# proto.net
KiCad netlist of a schematic drawn in EAGLE
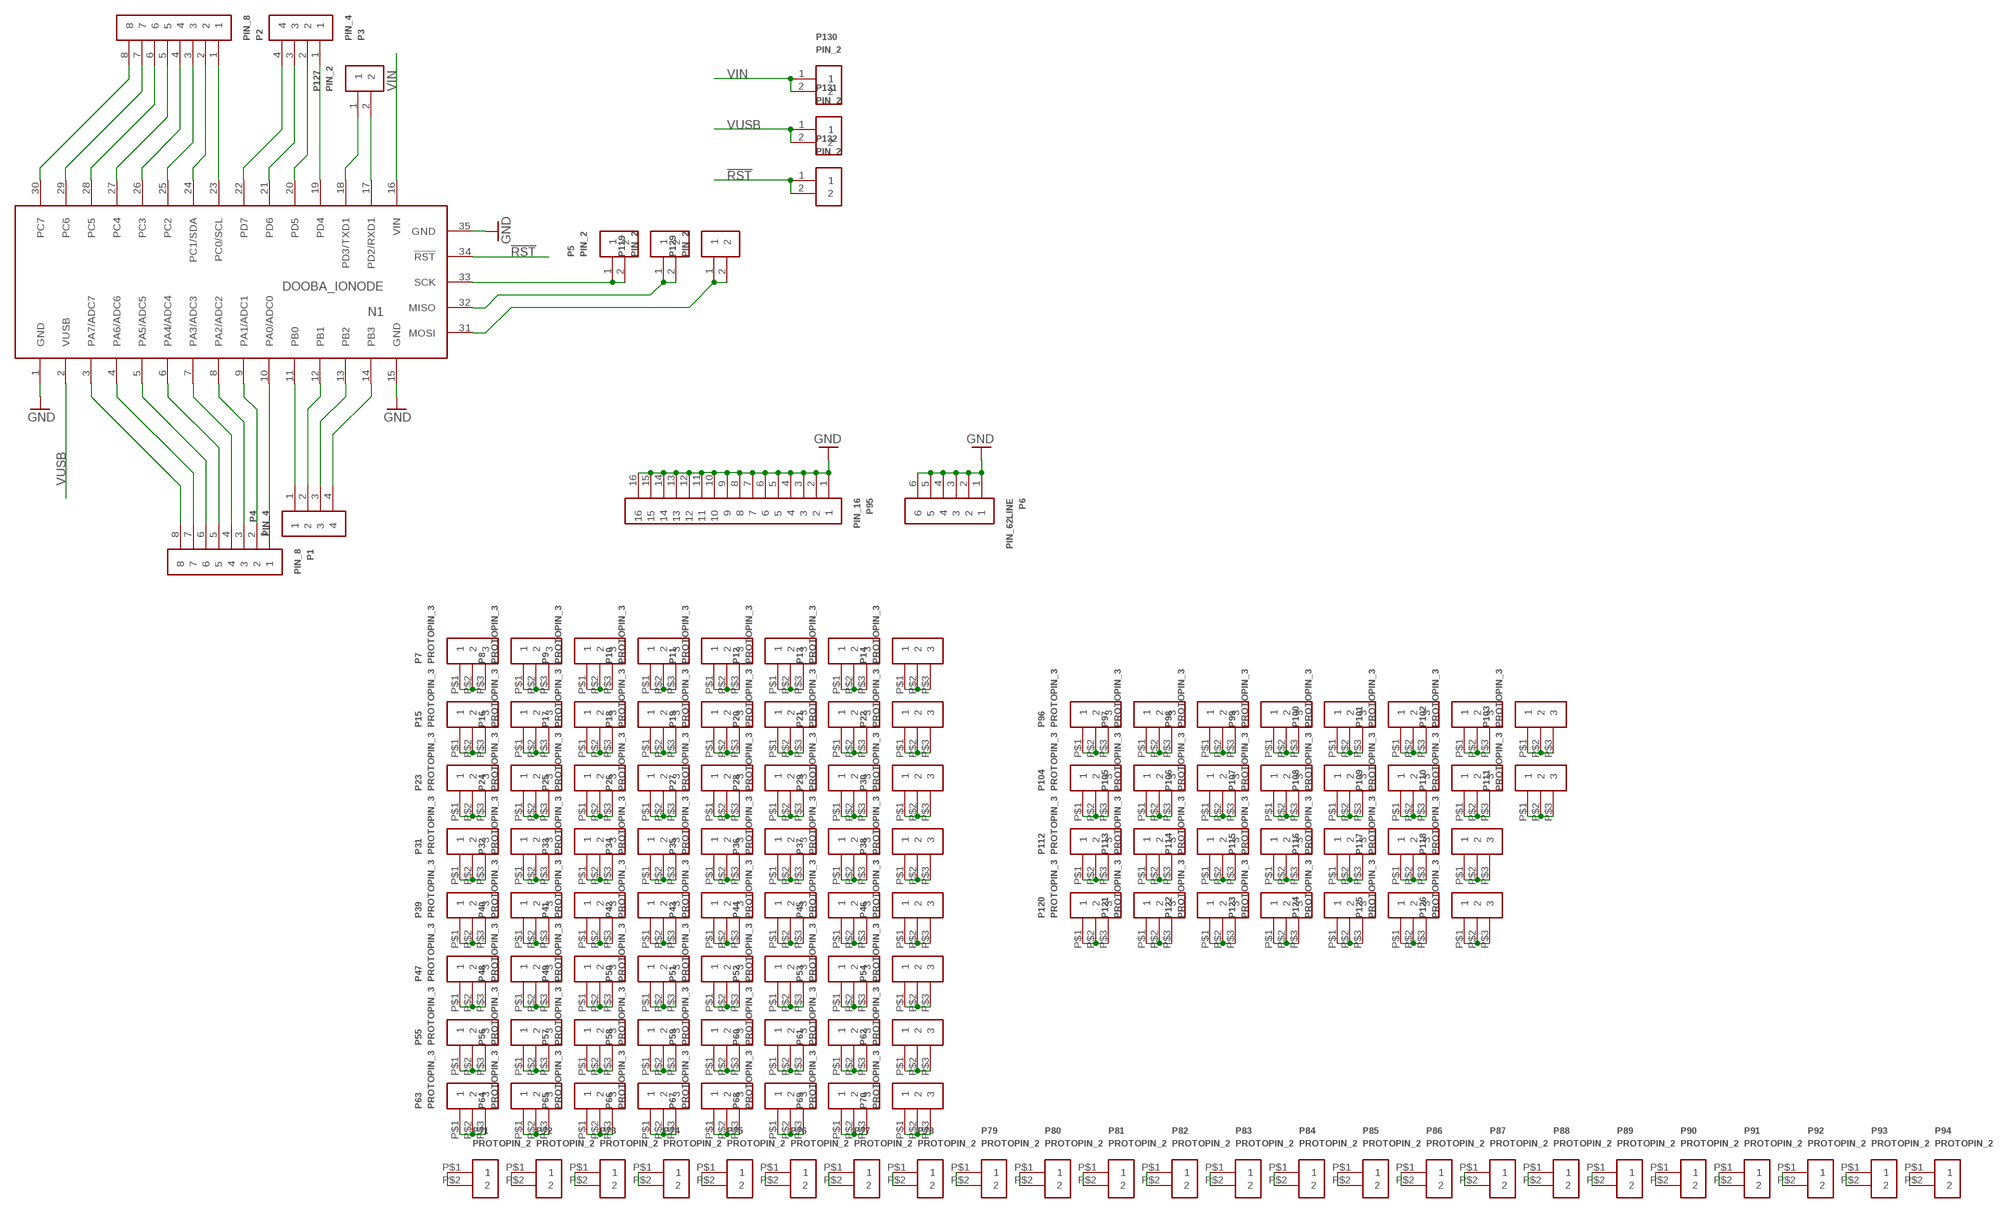
[diagram p0: schematic, sheet 1]

(export (version "E")
  (design (tool "Eeschema 10.0.6"))
  (components
    (comp (ref "N1")
      (value "DOOBA_IONODE")
      (footprint "eagle-import:DOOBA_IONODE")
      (libsource (lib "eagle-import") (part "DOOBA_IONODE"))
    )
    (comp (ref "P1")
      (value "PIN_8")
      (footprint "eagle-import:PIN_8")
      (libsource (lib "eagle-import") (part "PIN_8"))
    )
    (comp (ref "P2")
      (value "PIN_8")
      (footprint "eagle-import:PIN_8")
      (libsource (lib "eagle-import") (part "PIN_8"))
    )
    (comp (ref "P3")
      (value "PIN_4")
      (footprint "eagle-import:PIN_4")
      (libsource (lib "eagle-import") (part "PIN_4"))
    )
    (comp (ref "P4")
      (value "PIN_4")
      (footprint "eagle-import:PIN_4")
      (libsource (lib "eagle-import") (part "PIN_4"))
    )
    (comp (ref "P5")
      (value "PIN_2")
      (footprint "eagle-import:PIN_2")
      (libsource (lib "eagle-import") (part "PIN_2"))
    )
    (comp (ref "P6")
      (value "PIN_62LINE")
      (footprint "eagle-import:PIN_3X2")
      (libsource (lib "eagle-import") (part "PIN_62LINE"))
    )
    (comp (ref "P7")
      (value "PROTOPIN_3")
      (footprint "eagle-import:PROTOPIN_3")
      (libsource (lib "eagle-import") (part "PROTOPIN_3"))
    )
    (comp (ref "P8")
      (value "PROTOPIN_3")
      (footprint "eagle-import:PROTOPIN_3")
      (libsource (lib "eagle-import") (part "PROTOPIN_3"))
    )
    (comp (ref "P9")
      (value "PROTOPIN_3")
      (footprint "eagle-import:PROTOPIN_3")
      (libsource (lib "eagle-import") (part "PROTOPIN_3"))
    )
    (comp (ref "P10")
      (value "PROTOPIN_3")
      (footprint "eagle-import:PROTOPIN_3")
      (libsource (lib "eagle-import") (part "PROTOPIN_3"))
    )
    (comp (ref "P11")
      (value "PROTOPIN_3")
      (footprint "eagle-import:PROTOPIN_3")
      (libsource (lib "eagle-import") (part "PROTOPIN_3"))
    )
    (comp (ref "P12")
      (value "PROTOPIN_3")
      (footprint "eagle-import:PROTOPIN_3")
      (libsource (lib "eagle-import") (part "PROTOPIN_3"))
    )
    (comp (ref "P13")
      (value "PROTOPIN_3")
      (footprint "eagle-import:PROTOPIN_3")
      (libsource (lib "eagle-import") (part "PROTOPIN_3"))
    )
    (comp (ref "P14")
      (value "PROTOPIN_3")
      (footprint "eagle-import:PROTOPIN_3")
      (libsource (lib "eagle-import") (part "PROTOPIN_3"))
    )
    (comp (ref "P15")
      (value "PROTOPIN_3")
      (footprint "eagle-import:PROTOPIN_3")
      (libsource (lib "eagle-import") (part "PROTOPIN_3"))
    )
    (comp (ref "P16")
      (value "PROTOPIN_3")
      (footprint "eagle-import:PROTOPIN_3")
      (libsource (lib "eagle-import") (part "PROTOPIN_3"))
    )
    (comp (ref "P17")
      (value "PROTOPIN_3")
      (footprint "eagle-import:PROTOPIN_3")
      (libsource (lib "eagle-import") (part "PROTOPIN_3"))
    )
    (comp (ref "P18")
      (value "PROTOPIN_3")
      (footprint "eagle-import:PROTOPIN_3")
      (libsource (lib "eagle-import") (part "PROTOPIN_3"))
    )
    (comp (ref "P19")
      (value "PROTOPIN_3")
      (footprint "eagle-import:PROTOPIN_3")
      (libsource (lib "eagle-import") (part "PROTOPIN_3"))
    )
    (comp (ref "P20")
      (value "PROTOPIN_3")
      (footprint "eagle-import:PROTOPIN_3")
      (libsource (lib "eagle-import") (part "PROTOPIN_3"))
    )
    (comp (ref "P21")
      (value "PROTOPIN_3")
      (footprint "eagle-import:PROTOPIN_3")
      (libsource (lib "eagle-import") (part "PROTOPIN_3"))
    )
    (comp (ref "P22")
      (value "PROTOPIN_3")
      (footprint "eagle-import:PROTOPIN_3")
      (libsource (lib "eagle-import") (part "PROTOPIN_3"))
    )
    (comp (ref "P23")
      (value "PROTOPIN_3")
      (footprint "eagle-import:PROTOPIN_3")
      (libsource (lib "eagle-import") (part "PROTOPIN_3"))
    )
    (comp (ref "P24")
      (value "PROTOPIN_3")
      (footprint "eagle-import:PROTOPIN_3")
      (libsource (lib "eagle-import") (part "PROTOPIN_3"))
    )
    (comp (ref "P25")
      (value "PROTOPIN_3")
      (footprint "eagle-import:PROTOPIN_3")
      (libsource (lib "eagle-import") (part "PROTOPIN_3"))
    )
    (comp (ref "P26")
      (value "PROTOPIN_3")
      (footprint "eagle-import:PROTOPIN_3")
      (libsource (lib "eagle-import") (part "PROTOPIN_3"))
    )
    (comp (ref "P27")
      (value "PROTOPIN_3")
      (footprint "eagle-import:PROTOPIN_3")
      (libsource (lib "eagle-import") (part "PROTOPIN_3"))
    )
    (comp (ref "P28")
      (value "PROTOPIN_3")
      (footprint "eagle-import:PROTOPIN_3")
      (libsource (lib "eagle-import") (part "PROTOPIN_3"))
    )
    (comp (ref "P29")
      (value "PROTOPIN_3")
      (footprint "eagle-import:PROTOPIN_3")
      (libsource (lib "eagle-import") (part "PROTOPIN_3"))
    )
    (comp (ref "P30")
      (value "PROTOPIN_3")
      (footprint "eagle-import:PROTOPIN_3")
      (libsource (lib "eagle-import") (part "PROTOPIN_3"))
    )
    (comp (ref "P31")
      (value "PROTOPIN_3")
      (footprint "eagle-import:PROTOPIN_3")
      (libsource (lib "eagle-import") (part "PROTOPIN_3"))
    )
    (comp (ref "P32")
      (value "PROTOPIN_3")
      (footprint "eagle-import:PROTOPIN_3")
      (libsource (lib "eagle-import") (part "PROTOPIN_3"))
    )
    (comp (ref "P33")
      (value "PROTOPIN_3")
      (footprint "eagle-import:PROTOPIN_3")
      (libsource (lib "eagle-import") (part "PROTOPIN_3"))
    )
    (comp (ref "P34")
      (value "PROTOPIN_3")
      (footprint "eagle-import:PROTOPIN_3")
      (libsource (lib "eagle-import") (part "PROTOPIN_3"))
    )
    (comp (ref "P35")
      (value "PROTOPIN_3")
      (footprint "eagle-import:PROTOPIN_3")
      (libsource (lib "eagle-import") (part "PROTOPIN_3"))
    )
    (comp (ref "P36")
      (value "PROTOPIN_3")
      (footprint "eagle-import:PROTOPIN_3")
      (libsource (lib "eagle-import") (part "PROTOPIN_3"))
    )
    (comp (ref "P37")
      (value "PROTOPIN_3")
      (footprint "eagle-import:PROTOPIN_3")
      (libsource (lib "eagle-import") (part "PROTOPIN_3"))
    )
    (comp (ref "P38")
      (value "PROTOPIN_3")
      (footprint "eagle-import:PROTOPIN_3")
      (libsource (lib "eagle-import") (part "PROTOPIN_3"))
    )
    (comp (ref "P39")
      (value "PROTOPIN_3")
      (footprint "eagle-import:PROTOPIN_3")
      (libsource (lib "eagle-import") (part "PROTOPIN_3"))
    )
    (comp (ref "P40")
      (value "PROTOPIN_3")
      (footprint "eagle-import:PROTOPIN_3")
      (libsource (lib "eagle-import") (part "PROTOPIN_3"))
    )
    (comp (ref "P41")
      (value "PROTOPIN_3")
      (footprint "eagle-import:PROTOPIN_3")
      (libsource (lib "eagle-import") (part "PROTOPIN_3"))
    )
    (comp (ref "P42")
      (value "PROTOPIN_3")
      (footprint "eagle-import:PROTOPIN_3")
      (libsource (lib "eagle-import") (part "PROTOPIN_3"))
    )
    (comp (ref "P43")
      (value "PROTOPIN_3")
      (footprint "eagle-import:PROTOPIN_3")
      (libsource (lib "eagle-import") (part "PROTOPIN_3"))
    )
    (comp (ref "P44")
      (value "PROTOPIN_3")
      (footprint "eagle-import:PROTOPIN_3")
      (libsource (lib "eagle-import") (part "PROTOPIN_3"))
    )
    (comp (ref "P45")
      (value "PROTOPIN_3")
      (footprint "eagle-import:PROTOPIN_3")
      (libsource (lib "eagle-import") (part "PROTOPIN_3"))
    )
    (comp (ref "P46")
      (value "PROTOPIN_3")
      (footprint "eagle-import:PROTOPIN_3")
      (libsource (lib "eagle-import") (part "PROTOPIN_3"))
    )
    (comp (ref "P47")
      (value "PROTOPIN_3")
      (footprint "eagle-import:PROTOPIN_3")
      (libsource (lib "eagle-import") (part "PROTOPIN_3"))
    )
    (comp (ref "P48")
      (value "PROTOPIN_3")
      (footprint "eagle-import:PROTOPIN_3")
      (libsource (lib "eagle-import") (part "PROTOPIN_3"))
    )
    (comp (ref "P49")
      (value "PROTOPIN_3")
      (footprint "eagle-import:PROTOPIN_3")
      (libsource (lib "eagle-import") (part "PROTOPIN_3"))
    )
    (comp (ref "P50")
      (value "PROTOPIN_3")
      (footprint "eagle-import:PROTOPIN_3")
      (libsource (lib "eagle-import") (part "PROTOPIN_3"))
    )
    (comp (ref "P51")
      (value "PROTOPIN_3")
      (footprint "eagle-import:PROTOPIN_3")
      (libsource (lib "eagle-import") (part "PROTOPIN_3"))
    )
    (comp (ref "P52")
      (value "PROTOPIN_3")
      (footprint "eagle-import:PROTOPIN_3")
      (libsource (lib "eagle-import") (part "PROTOPIN_3"))
    )
    (comp (ref "P53")
      (value "PROTOPIN_3")
      (footprint "eagle-import:PROTOPIN_3")
      (libsource (lib "eagle-import") (part "PROTOPIN_3"))
    )
    (comp (ref "P54")
      (value "PROTOPIN_3")
      (footprint "eagle-import:PROTOPIN_3")
      (libsource (lib "eagle-import") (part "PROTOPIN_3"))
    )
    (comp (ref "P55")
      (value "PROTOPIN_3")
      (footprint "eagle-import:PROTOPIN_3")
      (libsource (lib "eagle-import") (part "PROTOPIN_3"))
    )
    (comp (ref "P56")
      (value "PROTOPIN_3")
      (footprint "eagle-import:PROTOPIN_3")
      (libsource (lib "eagle-import") (part "PROTOPIN_3"))
    )
    (comp (ref "P57")
      (value "PROTOPIN_3")
      (footprint "eagle-import:PROTOPIN_3")
      (libsource (lib "eagle-import") (part "PROTOPIN_3"))
    )
    (comp (ref "P58")
      (value "PROTOPIN_3")
      (footprint "eagle-import:PROTOPIN_3")
      (libsource (lib "eagle-import") (part "PROTOPIN_3"))
    )
    (comp (ref "P59")
      (value "PROTOPIN_3")
      (footprint "eagle-import:PROTOPIN_3")
      (libsource (lib "eagle-import") (part "PROTOPIN_3"))
    )
    (comp (ref "P60")
      (value "PROTOPIN_3")
      (footprint "eagle-import:PROTOPIN_3")
      (libsource (lib "eagle-import") (part "PROTOPIN_3"))
    )
    (comp (ref "P61")
      (value "PROTOPIN_3")
      (footprint "eagle-import:PROTOPIN_3")
      (libsource (lib "eagle-import") (part "PROTOPIN_3"))
    )
    (comp (ref "P62")
      (value "PROTOPIN_3")
      (footprint "eagle-import:PROTOPIN_3")
      (libsource (lib "eagle-import") (part "PROTOPIN_3"))
    )
    (comp (ref "P63")
      (value "PROTOPIN_3")
      (footprint "eagle-import:PROTOPIN_3")
      (libsource (lib "eagle-import") (part "PROTOPIN_3"))
    )
    (comp (ref "P64")
      (value "PROTOPIN_3")
      (footprint "eagle-import:PROTOPIN_3")
      (libsource (lib "eagle-import") (part "PROTOPIN_3"))
    )
    (comp (ref "P65")
      (value "PROTOPIN_3")
      (footprint "eagle-import:PROTOPIN_3")
      (libsource (lib "eagle-import") (part "PROTOPIN_3"))
    )
    (comp (ref "P66")
      (value "PROTOPIN_3")
      (footprint "eagle-import:PROTOPIN_3")
      (libsource (lib "eagle-import") (part "PROTOPIN_3"))
    )
    (comp (ref "P67")
      (value "PROTOPIN_3")
      (footprint "eagle-import:PROTOPIN_3")
      (libsource (lib "eagle-import") (part "PROTOPIN_3"))
    )
    (comp (ref "P68")
      (value "PROTOPIN_3")
      (footprint "eagle-import:PROTOPIN_3")
      (libsource (lib "eagle-import") (part "PROTOPIN_3"))
    )
    (comp (ref "P69")
      (value "PROTOPIN_3")
      (footprint "eagle-import:PROTOPIN_3")
      (libsource (lib "eagle-import") (part "PROTOPIN_3"))
    )
    (comp (ref "P70")
      (value "PROTOPIN_3")
      (footprint "eagle-import:PROTOPIN_3")
      (libsource (lib "eagle-import") (part "PROTOPIN_3"))
    )
    (comp (ref "P71")
      (value "PROTOPIN_2")
      (footprint "eagle-import:PROTOPIN_2")
      (libsource (lib "eagle-import") (part "PROTOPIN_2"))
    )
    (comp (ref "P72")
      (value "PROTOPIN_2")
      (footprint "eagle-import:PROTOPIN_2")
      (libsource (lib "eagle-import") (part "PROTOPIN_2"))
    )
    (comp (ref "P73")
      (value "PROTOPIN_2")
      (footprint "eagle-import:PROTOPIN_2")
      (libsource (lib "eagle-import") (part "PROTOPIN_2"))
    )
    (comp (ref "P74")
      (value "PROTOPIN_2")
      (footprint "eagle-import:PROTOPIN_2")
      (libsource (lib "eagle-import") (part "PROTOPIN_2"))
    )
    (comp (ref "P75")
      (value "PROTOPIN_2")
      (footprint "eagle-import:PROTOPIN_2")
      (libsource (lib "eagle-import") (part "PROTOPIN_2"))
    )
    (comp (ref "P76")
      (value "PROTOPIN_2")
      (footprint "eagle-import:PROTOPIN_2")
      (libsource (lib "eagle-import") (part "PROTOPIN_2"))
    )
    (comp (ref "P77")
      (value "PROTOPIN_2")
      (footprint "eagle-import:PROTOPIN_2")
      (libsource (lib "eagle-import") (part "PROTOPIN_2"))
    )
    (comp (ref "P78")
      (value "PROTOPIN_2")
      (footprint "eagle-import:PROTOPIN_2")
      (libsource (lib "eagle-import") (part "PROTOPIN_2"))
    )
    (comp (ref "P79")
      (value "PROTOPIN_2")
      (footprint "eagle-import:PROTOPIN_2")
      (libsource (lib "eagle-import") (part "PROTOPIN_2"))
    )
    (comp (ref "P80")
      (value "PROTOPIN_2")
      (footprint "eagle-import:PROTOPIN_2")
      (libsource (lib "eagle-import") (part "PROTOPIN_2"))
    )
    (comp (ref "P81")
      (value "PROTOPIN_2")
      (footprint "eagle-import:PROTOPIN_2")
      (libsource (lib "eagle-import") (part "PROTOPIN_2"))
    )
    (comp (ref "P82")
      (value "PROTOPIN_2")
      (footprint "eagle-import:PROTOPIN_2")
      (libsource (lib "eagle-import") (part "PROTOPIN_2"))
    )
    (comp (ref "P83")
      (value "PROTOPIN_2")
      (footprint "eagle-import:PROTOPIN_2")
      (libsource (lib "eagle-import") (part "PROTOPIN_2"))
    )
    (comp (ref "P84")
      (value "PROTOPIN_2")
      (footprint "eagle-import:PROTOPIN_2")
      (libsource (lib "eagle-import") (part "PROTOPIN_2"))
    )
    (comp (ref "P85")
      (value "PROTOPIN_2")
      (footprint "eagle-import:PROTOPIN_2")
      (libsource (lib "eagle-import") (part "PROTOPIN_2"))
    )
    (comp (ref "P86")
      (value "PROTOPIN_2")
      (footprint "eagle-import:PROTOPIN_2")
      (libsource (lib "eagle-import") (part "PROTOPIN_2"))
    )
    (comp (ref "P87")
      (value "PROTOPIN_2")
      (footprint "eagle-import:PROTOPIN_2")
      (libsource (lib "eagle-import") (part "PROTOPIN_2"))
    )
    (comp (ref "P88")
      (value "PROTOPIN_2")
      (footprint "eagle-import:PROTOPIN_2")
      (libsource (lib "eagle-import") (part "PROTOPIN_2"))
    )
    (comp (ref "P89")
      (value "PROTOPIN_2")
      (footprint "eagle-import:PROTOPIN_2")
      (libsource (lib "eagle-import") (part "PROTOPIN_2"))
    )
    (comp (ref "P90")
      (value "PROTOPIN_2")
      (footprint "eagle-import:PROTOPIN_2")
      (libsource (lib "eagle-import") (part "PROTOPIN_2"))
    )
    (comp (ref "P91")
      (value "PROTOPIN_2")
      (footprint "eagle-import:PROTOPIN_2")
      (libsource (lib "eagle-import") (part "PROTOPIN_2"))
    )
    (comp (ref "P92")
      (value "PROTOPIN_2")
      (footprint "eagle-import:PROTOPIN_2")
      (libsource (lib "eagle-import") (part "PROTOPIN_2"))
    )
    (comp (ref "P93")
      (value "PROTOPIN_2")
      (footprint "eagle-import:PROTOPIN_2")
      (libsource (lib "eagle-import") (part "PROTOPIN_2"))
    )
    (comp (ref "P94")
      (value "PROTOPIN_2")
      (footprint "eagle-import:PROTOPIN_2")
      (libsource (lib "eagle-import") (part "PROTOPIN_2"))
    )
    (comp (ref "P95")
      (value "PIN_16")
      (footprint "eagle-import:PIN_16")
      (libsource (lib "eagle-import") (part "PIN_16"))
    )
    (comp (ref "P96")
      (value "PROTOPIN_3")
      (footprint "eagle-import:PROTOPIN_3")
      (libsource (lib "eagle-import") (part "PROTOPIN_3"))
    )
    (comp (ref "P97")
      (value "PROTOPIN_3")
      (footprint "eagle-import:PROTOPIN_3")
      (libsource (lib "eagle-import") (part "PROTOPIN_3"))
    )
    (comp (ref "P98")
      (value "PROTOPIN_3")
      (footprint "eagle-import:PROTOPIN_3")
      (libsource (lib "eagle-import") (part "PROTOPIN_3"))
    )
    (comp (ref "P99")
      (value "PROTOPIN_3")
      (footprint "eagle-import:PROTOPIN_3")
      (libsource (lib "eagle-import") (part "PROTOPIN_3"))
    )
    (comp (ref "P100")
      (value "PROTOPIN_3")
      (footprint "eagle-import:PROTOPIN_3")
      (libsource (lib "eagle-import") (part "PROTOPIN_3"))
    )
    (comp (ref "P101")
      (value "PROTOPIN_3")
      (footprint "eagle-import:PROTOPIN_3")
      (libsource (lib "eagle-import") (part "PROTOPIN_3"))
    )
    (comp (ref "P102")
      (value "PROTOPIN_3")
      (footprint "eagle-import:PROTOPIN_3")
      (libsource (lib "eagle-import") (part "PROTOPIN_3"))
    )
    (comp (ref "P103")
      (value "PROTOPIN_3")
      (footprint "eagle-import:PROTOPIN_3")
      (libsource (lib "eagle-import") (part "PROTOPIN_3"))
    )
    (comp (ref "P104")
      (value "PROTOPIN_3")
      (footprint "eagle-import:PROTOPIN_3")
      (libsource (lib "eagle-import") (part "PROTOPIN_3"))
    )
    (comp (ref "P105")
      (value "PROTOPIN_3")
      (footprint "eagle-import:PROTOPIN_3")
      (libsource (lib "eagle-import") (part "PROTOPIN_3"))
    )
    (comp (ref "P106")
      (value "PROTOPIN_3")
      (footprint "eagle-import:PROTOPIN_3")
      (libsource (lib "eagle-import") (part "PROTOPIN_3"))
    )
    (comp (ref "P107")
      (value "PROTOPIN_3")
      (footprint "eagle-import:PROTOPIN_3")
      (libsource (lib "eagle-import") (part "PROTOPIN_3"))
    )
    (comp (ref "P108")
      (value "PROTOPIN_3")
      (footprint "eagle-import:PROTOPIN_3")
      (libsource (lib "eagle-import") (part "PROTOPIN_3"))
    )
    (comp (ref "P109")
      (value "PROTOPIN_3")
      (footprint "eagle-import:PROTOPIN_3")
      (libsource (lib "eagle-import") (part "PROTOPIN_3"))
    )
    (comp (ref "P110")
      (value "PROTOPIN_3")
      (footprint "eagle-import:PROTOPIN_3")
      (libsource (lib "eagle-import") (part "PROTOPIN_3"))
    )
    (comp (ref "P111")
      (value "PROTOPIN_3")
      (footprint "eagle-import:PROTOPIN_3")
      (libsource (lib "eagle-import") (part "PROTOPIN_3"))
    )
    (comp (ref "P112")
      (value "PROTOPIN_3")
      (footprint "eagle-import:PROTOPIN_3")
      (libsource (lib "eagle-import") (part "PROTOPIN_3"))
    )
    (comp (ref "P113")
      (value "PROTOPIN_3")
      (footprint "eagle-import:PROTOPIN_3")
      (libsource (lib "eagle-import") (part "PROTOPIN_3"))
    )
    (comp (ref "P114")
      (value "PROTOPIN_3")
      (footprint "eagle-import:PROTOPIN_3")
      (libsource (lib "eagle-import") (part "PROTOPIN_3"))
    )
    (comp (ref "P115")
      (value "PROTOPIN_3")
      (footprint "eagle-import:PROTOPIN_3")
      (libsource (lib "eagle-import") (part "PROTOPIN_3"))
    )
    (comp (ref "P116")
      (value "PROTOPIN_3")
      (footprint "eagle-import:PROTOPIN_3")
      (libsource (lib "eagle-import") (part "PROTOPIN_3"))
    )
    (comp (ref "P117")
      (value "PROTOPIN_3")
      (footprint "eagle-import:PROTOPIN_3")
      (libsource (lib "eagle-import") (part "PROTOPIN_3"))
    )
    (comp (ref "P118")
      (value "PROTOPIN_3")
      (footprint "eagle-import:PROTOPIN_3")
      (libsource (lib "eagle-import") (part "PROTOPIN_3"))
    )
    (comp (ref "P119")
      (value "PIN_2")
      (footprint "eagle-import:PIN_2")
      (libsource (lib "eagle-import") (part "PIN_2"))
    )
    (comp (ref "P120")
      (value "PROTOPIN_3")
      (footprint "eagle-import:PROTOPIN_3")
      (libsource (lib "eagle-import") (part "PROTOPIN_3"))
    )
    (comp (ref "P121")
      (value "PROTOPIN_3")
      (footprint "eagle-import:PROTOPIN_3")
      (libsource (lib "eagle-import") (part "PROTOPIN_3"))
    )
    (comp (ref "P122")
      (value "PROTOPIN_3")
      (footprint "eagle-import:PROTOPIN_3")
      (libsource (lib "eagle-import") (part "PROTOPIN_3"))
    )
    (comp (ref "P123")
      (value "PROTOPIN_3")
      (footprint "eagle-import:PROTOPIN_3")
      (libsource (lib "eagle-import") (part "PROTOPIN_3"))
    )
    (comp (ref "P124")
      (value "PROTOPIN_3")
      (footprint "eagle-import:PROTOPIN_3")
      (libsource (lib "eagle-import") (part "PROTOPIN_3"))
    )
    (comp (ref "P125")
      (value "PROTOPIN_3")
      (footprint "eagle-import:PROTOPIN_3")
      (libsource (lib "eagle-import") (part "PROTOPIN_3"))
    )
    (comp (ref "P126")
      (value "PROTOPIN_3")
      (footprint "eagle-import:PROTOPIN_3")
      (libsource (lib "eagle-import") (part "PROTOPIN_3"))
    )
    (comp (ref "P127")
      (value "PIN_2")
      (footprint "eagle-import:PIN_2")
      (libsource (lib "eagle-import") (part "PIN_2"))
    )
    (comp (ref "P129")
      (value "PIN_2")
      (footprint "eagle-import:PIN_2")
      (libsource (lib "eagle-import") (part "PIN_2"))
    )
    (comp (ref "P130")
      (value "PIN_2")
      (footprint "eagle-import:PIN_2")
      (libsource (lib "eagle-import") (part "PIN_2"))
    )
    (comp (ref "P131")
      (value "PIN_2")
      (footprint "eagle-import:PIN_2")
      (libsource (lib "eagle-import") (part "PIN_2"))
    )
    (comp (ref "P132")
      (value "PIN_2")
      (footprint "eagle-import:PIN_2")
      (libsource (lib "eagle-import") (part "PIN_2"))
    )
  )
  (nets
    (net (code "1") (name "/VIN") (class "Default")
      (node (ref "N1") (pin "16") (pinfunction "VIN_16") (pintype "bidirectional"))
      (node (ref "P130") (pin "1") (pinfunction "1_1") (pintype "bidirectional"))
      (node (ref "P130") (pin "2") (pinfunction "2_2") (pintype "bidirectional"))
    )
    (net (code "2") (name "/VUSB") (class "Default")
      (node (ref "N1") (pin "2") (pinfunction "VUSB_2") (pintype "bidirectional"))
      (node (ref "P131") (pin "1") (pinfunction "1_1") (pintype "bidirectional"))
      (node (ref "P131") (pin "2") (pinfunction "2_2") (pintype "bidirectional"))
    )
    (net (code "3") (name "/~{RST}") (class "Default")
      (node (ref "N1") (pin "34") (pinfunction "~{RST}_34") (pintype "bidirectional"))
      (node (ref "P132") (pin "1") (pinfunction "1_1") (pintype "bidirectional"))
      (node (ref "P132") (pin "2") (pinfunction "2_2") (pintype "bidirectional"))
    )
    (net (code "4") (name "GND") (class "Default")
      (node (ref "N1") (pin "1") (pinfunction "GND_1") (pintype "bidirectional"))
      (node (ref "N1") (pin "15") (pinfunction "GND_15") (pintype "bidirectional"))
      (node (ref "N1") (pin "35") (pinfunction "GND_35") (pintype "bidirectional"))
      (node (ref "P6") (pin "1") (pinfunction "1_1") (pintype "bidirectional"))
      (node (ref "P6") (pin "2") (pinfunction "2_2") (pintype "bidirectional"))
      (node (ref "P6") (pin "3") (pinfunction "3_3") (pintype "bidirectional"))
      (node (ref "P6") (pin "4") (pinfunction "4_4") (pintype "bidirectional"))
      (node (ref "P6") (pin "5") (pinfunction "5_5") (pintype "bidirectional"))
      (node (ref "P6") (pin "6") (pinfunction "6_6") (pintype "bidirectional"))
      (node (ref "P95") (pin "1") (pinfunction "1_1") (pintype "bidirectional"))
      (node (ref "P95") (pin "10") (pinfunction "10_10") (pintype "bidirectional"))
      (node (ref "P95") (pin "11") (pinfunction "11_11") (pintype "bidirectional"))
      (node (ref "P95") (pin "12") (pinfunction "12_12") (pintype "bidirectional"))
      (node (ref "P95") (pin "13") (pinfunction "13_13") (pintype "bidirectional"))
      (node (ref "P95") (pin "14") (pinfunction "14_14") (pintype "bidirectional"))
      (node (ref "P95") (pin "15") (pinfunction "15_15") (pintype "bidirectional"))
      (node (ref "P95") (pin "16") (pinfunction "16_16") (pintype "bidirectional"))
      (node (ref "P95") (pin "2") (pinfunction "2_2") (pintype "bidirectional"))
      (node (ref "P95") (pin "3") (pinfunction "3_3") (pintype "bidirectional"))
      (node (ref "P95") (pin "4") (pinfunction "4_4") (pintype "bidirectional"))
      (node (ref "P95") (pin "5") (pinfunction "5_5") (pintype "bidirectional"))
      (node (ref "P95") (pin "6") (pinfunction "6_6") (pintype "bidirectional"))
      (node (ref "P95") (pin "7") (pinfunction "7_7") (pintype "bidirectional"))
      (node (ref "P95") (pin "8") (pinfunction "8_8") (pintype "bidirectional"))
      (node (ref "P95") (pin "9") (pinfunction "9_9") (pintype "bidirectional"))
    )
    (net (code "5") (name "Net-(N1-MISO)") (class "Default")
      (node (ref "N1") (pin "32") (pinfunction "MISO_32") (pintype "bidirectional"))
      (node (ref "P119") (pin "1") (pinfunction "1_1") (pintype "bidirectional"))
      (node (ref "P119") (pin "2") (pinfunction "2_2") (pintype "bidirectional"))
    )
    (net (code "6") (name "Net-(N1-MOSI)") (class "Default")
      (node (ref "N1") (pin "31") (pinfunction "MOSI_31") (pintype "bidirectional"))
      (node (ref "P129") (pin "1") (pinfunction "1_1") (pintype "bidirectional"))
      (node (ref "P129") (pin "2") (pinfunction "2_2") (pintype "bidirectional"))
    )
    (net (code "7") (name "Net-(N1-PA0{slash}ADC0)") (class "Default")
      (node (ref "N1") (pin "10") (pinfunction "PA0/ADC0_10") (pintype "bidirectional"))
      (node (ref "P1") (pin "1") (pinfunction "1_1") (pintype "bidirectional"))
    )
    (net (code "8") (name "Net-(N1-PA1{slash}ADC1)") (class "Default")
      (node (ref "N1") (pin "9") (pinfunction "PA1/ADC1_9") (pintype "bidirectional"))
      (node (ref "P1") (pin "2") (pinfunction "2_2") (pintype "bidirectional"))
    )
    (net (code "9") (name "Net-(N1-PA2{slash}ADC2)") (class "Default")
      (node (ref "N1") (pin "8") (pinfunction "PA2/ADC2_8") (pintype "bidirectional"))
      (node (ref "P1") (pin "3") (pinfunction "3_3") (pintype "bidirectional"))
    )
    (net (code "10") (name "Net-(N1-PA3{slash}ADC3)") (class "Default")
      (node (ref "N1") (pin "7") (pinfunction "PA3/ADC3_7") (pintype "bidirectional"))
      (node (ref "P1") (pin "4") (pinfunction "4_4") (pintype "bidirectional"))
    )
    (net (code "11") (name "Net-(N1-PA4{slash}ADC4)") (class "Default")
      (node (ref "N1") (pin "6") (pinfunction "PA4/ADC4_6") (pintype "bidirectional"))
      (node (ref "P1") (pin "5") (pinfunction "5_5") (pintype "bidirectional"))
    )
    (net (code "12") (name "Net-(N1-PA5{slash}ADC5)") (class "Default")
      (node (ref "N1") (pin "5") (pinfunction "PA5/ADC5_5") (pintype "bidirectional"))
      (node (ref "P1") (pin "6") (pinfunction "6_6") (pintype "bidirectional"))
    )
    (net (code "13") (name "Net-(N1-PA6{slash}ADC6)") (class "Default")
      (node (ref "N1") (pin "4") (pinfunction "PA6/ADC6_4") (pintype "bidirectional"))
      (node (ref "P1") (pin "7") (pinfunction "7_7") (pintype "bidirectional"))
    )
    (net (code "14") (name "Net-(N1-PA7{slash}ADC7)") (class "Default")
      (node (ref "N1") (pin "3") (pinfunction "PA7/ADC7_3") (pintype "bidirectional"))
      (node (ref "P1") (pin "8") (pinfunction "8_8") (pintype "bidirectional"))
    )
    (net (code "15") (name "Net-(N1-PB0)") (class "Default")
      (node (ref "N1") (pin "11") (pinfunction "PB0_11") (pintype "bidirectional"))
      (node (ref "P4") (pin "1") (pinfunction "1_1") (pintype "bidirectional"))
    )
    (net (code "16") (name "Net-(N1-PB1)") (class "Default")
      (node (ref "N1") (pin "12") (pinfunction "PB1_12") (pintype "bidirectional"))
      (node (ref "P4") (pin "2") (pinfunction "2_2") (pintype "bidirectional"))
    )
    (net (code "17") (name "Net-(N1-PB2)") (class "Default")
      (node (ref "N1") (pin "13") (pinfunction "PB2_13") (pintype "bidirectional"))
      (node (ref "P4") (pin "3") (pinfunction "3_3") (pintype "bidirectional"))
    )
    (net (code "18") (name "Net-(N1-PB3)") (class "Default")
      (node (ref "N1") (pin "14") (pinfunction "PB3_14") (pintype "bidirectional"))
      (node (ref "P4") (pin "4") (pinfunction "4_4") (pintype "bidirectional"))
    )
    (net (code "19") (name "Net-(N1-PC0{slash}SCL)") (class "Default")
      (node (ref "N1") (pin "23") (pinfunction "PC0/SCL_23") (pintype "bidirectional"))
      (node (ref "P2") (pin "1") (pinfunction "1_1") (pintype "bidirectional"))
    )
    (net (code "20") (name "Net-(N1-PC1{slash}SDA)") (class "Default")
      (node (ref "N1") (pin "24") (pinfunction "PC1/SDA_24") (pintype "bidirectional"))
      (node (ref "P2") (pin "2") (pinfunction "2_2") (pintype "bidirectional"))
    )
    (net (code "21") (name "Net-(N1-PC2)") (class "Default")
      (node (ref "N1") (pin "25") (pinfunction "PC2_25") (pintype "bidirectional"))
      (node (ref "P2") (pin "3") (pinfunction "3_3") (pintype "bidirectional"))
    )
    (net (code "22") (name "Net-(N1-PC3)") (class "Default")
      (node (ref "N1") (pin "26") (pinfunction "PC3_26") (pintype "bidirectional"))
      (node (ref "P2") (pin "4") (pinfunction "4_4") (pintype "bidirectional"))
    )
    (net (code "23") (name "Net-(N1-PC4)") (class "Default")
      (node (ref "N1") (pin "27") (pinfunction "PC4_27") (pintype "bidirectional"))
      (node (ref "P2") (pin "5") (pinfunction "5_5") (pintype "bidirectional"))
    )
    (net (code "24") (name "Net-(N1-PC5)") (class "Default")
      (node (ref "N1") (pin "28") (pinfunction "PC5_28") (pintype "bidirectional"))
      (node (ref "P2") (pin "6") (pinfunction "6_6") (pintype "bidirectional"))
    )
    (net (code "25") (name "Net-(N1-PC6)") (class "Default")
      (node (ref "N1") (pin "29") (pinfunction "PC6_29") (pintype "bidirectional"))
      (node (ref "P2") (pin "7") (pinfunction "7_7") (pintype "bidirectional"))
    )
    (net (code "26") (name "Net-(N1-PC7)") (class "Default")
      (node (ref "N1") (pin "30") (pinfunction "PC7_30") (pintype "bidirectional"))
      (node (ref "P2") (pin "8") (pinfunction "8_8") (pintype "bidirectional"))
    )
    (net (code "27") (name "Net-(N1-PD2{slash}RXD1)") (class "Default")
      (node (ref "N1") (pin "17") (pinfunction "PD2/RXD1_17") (pintype "bidirectional"))
      (node (ref "P127") (pin "2") (pinfunction "2_2") (pintype "bidirectional"))
    )
    (net (code "28") (name "Net-(N1-PD3{slash}TXD1)") (class "Default")
      (node (ref "N1") (pin "18") (pinfunction "PD3/TXD1_18") (pintype "bidirectional"))
      (node (ref "P127") (pin "1") (pinfunction "1_1") (pintype "bidirectional"))
    )
    (net (code "29") (name "Net-(N1-PD4)") (class "Default")
      (node (ref "N1") (pin "19") (pinfunction "PD4_19") (pintype "bidirectional"))
      (node (ref "P3") (pin "1") (pinfunction "1_1") (pintype "bidirectional"))
    )
    (net (code "30") (name "Net-(N1-PD5)") (class "Default")
      (node (ref "N1") (pin "20") (pinfunction "PD5_20") (pintype "bidirectional"))
      (node (ref "P3") (pin "2") (pinfunction "2_2") (pintype "bidirectional"))
    )
    (net (code "31") (name "Net-(N1-PD6)") (class "Default")
      (node (ref "N1") (pin "21") (pinfunction "PD6_21") (pintype "bidirectional"))
      (node (ref "P3") (pin "3") (pinfunction "3_3") (pintype "bidirectional"))
    )
    (net (code "32") (name "Net-(N1-PD7)") (class "Default")
      (node (ref "N1") (pin "22") (pinfunction "PD7_22") (pintype "bidirectional"))
      (node (ref "P3") (pin "4") (pinfunction "4_4") (pintype "bidirectional"))
    )
    (net (code "33") (name "Net-(N1-SCK)") (class "Default")
      (node (ref "N1") (pin "33") (pinfunction "SCK_33") (pintype "bidirectional"))
      (node (ref "P5") (pin "1") (pinfunction "1_1") (pintype "bidirectional"))
      (node (ref "P5") (pin "2") (pinfunction "2_2") (pintype "bidirectional"))
    )
    (net (code "34") (name "Net-(P7-1)") (class "Default")
      (node (ref "P7") (pin "P$1") (pinfunction "1_P$1") (pintype "bidirectional"))
      (node (ref "P7") (pin "P$2") (pinfunction "2_P$2") (pintype "bidirectional"))
      (node (ref "P7") (pin "P$3") (pinfunction "3_P$3") (pintype "bidirectional"))
    )
    (net (code "35") (name "Net-(P8-1)") (class "Default")
      (node (ref "P8") (pin "P$1") (pinfunction "1_P$1") (pintype "bidirectional"))
      (node (ref "P8") (pin "P$2") (pinfunction "2_P$2") (pintype "bidirectional"))
      (node (ref "P8") (pin "P$3") (pinfunction "3_P$3") (pintype "bidirectional"))
    )
    (net (code "36") (name "Net-(P9-1)") (class "Default")
      (node (ref "P9") (pin "P$1") (pinfunction "1_P$1") (pintype "bidirectional"))
      (node (ref "P9") (pin "P$2") (pinfunction "2_P$2") (pintype "bidirectional"))
      (node (ref "P9") (pin "P$3") (pinfunction "3_P$3") (pintype "bidirectional"))
    )
    (net (code "37") (name "Net-(P10-1)") (class "Default")
      (node (ref "P10") (pin "P$1") (pinfunction "1_P$1") (pintype "bidirectional"))
      (node (ref "P10") (pin "P$2") (pinfunction "2_P$2") (pintype "bidirectional"))
      (node (ref "P10") (pin "P$3") (pinfunction "3_P$3") (pintype "bidirectional"))
    )
    (net (code "38") (name "Net-(P11-1)") (class "Default")
      (node (ref "P11") (pin "P$1") (pinfunction "1_P$1") (pintype "bidirectional"))
      (node (ref "P11") (pin "P$2") (pinfunction "2_P$2") (pintype "bidirectional"))
      (node (ref "P11") (pin "P$3") (pinfunction "3_P$3") (pintype "bidirectional"))
    )
    (net (code "39") (name "Net-(P12-1)") (class "Default")
      (node (ref "P12") (pin "P$1") (pinfunction "1_P$1") (pintype "bidirectional"))
      (node (ref "P12") (pin "P$2") (pinfunction "2_P$2") (pintype "bidirectional"))
      (node (ref "P12") (pin "P$3") (pinfunction "3_P$3") (pintype "bidirectional"))
    )
    (net (code "40") (name "Net-(P13-1)") (class "Default")
      (node (ref "P13") (pin "P$1") (pinfunction "1_P$1") (pintype "bidirectional"))
      (node (ref "P13") (pin "P$2") (pinfunction "2_P$2") (pintype "bidirectional"))
      (node (ref "P13") (pin "P$3") (pinfunction "3_P$3") (pintype "bidirectional"))
    )
    (net (code "41") (name "Net-(P14-1)") (class "Default")
      (node (ref "P14") (pin "P$1") (pinfunction "1_P$1") (pintype "bidirectional"))
      (node (ref "P14") (pin "P$2") (pinfunction "2_P$2") (pintype "bidirectional"))
      (node (ref "P14") (pin "P$3") (pinfunction "3_P$3") (pintype "bidirectional"))
    )
    (net (code "42") (name "Net-(P15-1)") (class "Default")
      (node (ref "P15") (pin "P$1") (pinfunction "1_P$1") (pintype "bidirectional"))
      (node (ref "P15") (pin "P$2") (pinfunction "2_P$2") (pintype "bidirectional"))
      (node (ref "P15") (pin "P$3") (pinfunction "3_P$3") (pintype "bidirectional"))
    )
    (net (code "43") (name "Net-(P16-1)") (class "Default")
      (node (ref "P16") (pin "P$1") (pinfunction "1_P$1") (pintype "bidirectional"))
      (node (ref "P16") (pin "P$2") (pinfunction "2_P$2") (pintype "bidirectional"))
      (node (ref "P16") (pin "P$3") (pinfunction "3_P$3") (pintype "bidirectional"))
    )
    (net (code "44") (name "Net-(P17-1)") (class "Default")
      (node (ref "P17") (pin "P$1") (pinfunction "1_P$1") (pintype "bidirectional"))
      (node (ref "P17") (pin "P$2") (pinfunction "2_P$2") (pintype "bidirectional"))
      (node (ref "P17") (pin "P$3") (pinfunction "3_P$3") (pintype "bidirectional"))
    )
    (net (code "45") (name "Net-(P18-1)") (class "Default")
      (node (ref "P18") (pin "P$1") (pinfunction "1_P$1") (pintype "bidirectional"))
      (node (ref "P18") (pin "P$2") (pinfunction "2_P$2") (pintype "bidirectional"))
      (node (ref "P18") (pin "P$3") (pinfunction "3_P$3") (pintype "bidirectional"))
    )
    (net (code "46") (name "Net-(P19-1)") (class "Default")
      (node (ref "P19") (pin "P$1") (pinfunction "1_P$1") (pintype "bidirectional"))
      (node (ref "P19") (pin "P$2") (pinfunction "2_P$2") (pintype "bidirectional"))
      (node (ref "P19") (pin "P$3") (pinfunction "3_P$3") (pintype "bidirectional"))
    )
    (net (code "47") (name "Net-(P20-1)") (class "Default")
      (node (ref "P20") (pin "P$1") (pinfunction "1_P$1") (pintype "bidirectional"))
      (node (ref "P20") (pin "P$2") (pinfunction "2_P$2") (pintype "bidirectional"))
      (node (ref "P20") (pin "P$3") (pinfunction "3_P$3") (pintype "bidirectional"))
    )
    (net (code "48") (name "Net-(P21-1)") (class "Default")
      (node (ref "P21") (pin "P$1") (pinfunction "1_P$1") (pintype "bidirectional"))
      (node (ref "P21") (pin "P$2") (pinfunction "2_P$2") (pintype "bidirectional"))
      (node (ref "P21") (pin "P$3") (pinfunction "3_P$3") (pintype "bidirectional"))
    )
    (net (code "49") (name "Net-(P22-1)") (class "Default")
      (node (ref "P22") (pin "P$1") (pinfunction "1_P$1") (pintype "bidirectional"))
      (node (ref "P22") (pin "P$2") (pinfunction "2_P$2") (pintype "bidirectional"))
      (node (ref "P22") (pin "P$3") (pinfunction "3_P$3") (pintype "bidirectional"))
    )
    (net (code "50") (name "Net-(P23-1)") (class "Default")
      (node (ref "P23") (pin "P$1") (pinfunction "1_P$1") (pintype "bidirectional"))
      (node (ref "P23") (pin "P$2") (pinfunction "2_P$2") (pintype "bidirectional"))
      (node (ref "P23") (pin "P$3") (pinfunction "3_P$3") (pintype "bidirectional"))
    )
    (net (code "51") (name "Net-(P24-1)") (class "Default")
      (node (ref "P24") (pin "P$1") (pinfunction "1_P$1") (pintype "bidirectional"))
      (node (ref "P24") (pin "P$2") (pinfunction "2_P$2") (pintype "bidirectional"))
      (node (ref "P24") (pin "P$3") (pinfunction "3_P$3") (pintype "bidirectional"))
    )
    (net (code "52") (name "Net-(P25-1)") (class "Default")
      (node (ref "P25") (pin "P$1") (pinfunction "1_P$1") (pintype "bidirectional"))
      (node (ref "P25") (pin "P$2") (pinfunction "2_P$2") (pintype "bidirectional"))
      (node (ref "P25") (pin "P$3") (pinfunction "3_P$3") (pintype "bidirectional"))
    )
    (net (code "53") (name "Net-(P26-1)") (class "Default")
      (node (ref "P26") (pin "P$1") (pinfunction "1_P$1") (pintype "bidirectional"))
      (node (ref "P26") (pin "P$2") (pinfunction "2_P$2") (pintype "bidirectional"))
      (node (ref "P26") (pin "P$3") (pinfunction "3_P$3") (pintype "bidirectional"))
    )
    (net (code "54") (name "Net-(P27-1)") (class "Default")
      (node (ref "P27") (pin "P$1") (pinfunction "1_P$1") (pintype "bidirectional"))
      (node (ref "P27") (pin "P$2") (pinfunction "2_P$2") (pintype "bidirectional"))
      (node (ref "P27") (pin "P$3") (pinfunction "3_P$3") (pintype "bidirectional"))
    )
    (net (code "55") (name "Net-(P28-1)") (class "Default")
      (node (ref "P28") (pin "P$1") (pinfunction "1_P$1") (pintype "bidirectional"))
      (node (ref "P28") (pin "P$2") (pinfunction "2_P$2") (pintype "bidirectional"))
      (node (ref "P28") (pin "P$3") (pinfunction "3_P$3") (pintype "bidirectional"))
    )
    (net (code "56") (name "Net-(P29-1)") (class "Default")
      (node (ref "P29") (pin "P$1") (pinfunction "1_P$1") (pintype "bidirectional"))
      (node (ref "P29") (pin "P$2") (pinfunction "2_P$2") (pintype "bidirectional"))
      (node (ref "P29") (pin "P$3") (pinfunction "3_P$3") (pintype "bidirectional"))
    )
    (net (code "57") (name "Net-(P30-1)") (class "Default")
      (node (ref "P30") (pin "P$1") (pinfunction "1_P$1") (pintype "bidirectional"))
      (node (ref "P30") (pin "P$2") (pinfunction "2_P$2") (pintype "bidirectional"))
      (node (ref "P30") (pin "P$3") (pinfunction "3_P$3") (pintype "bidirectional"))
    )
    (net (code "58") (name "Net-(P31-1)") (class "Default")
      (node (ref "P31") (pin "P$1") (pinfunction "1_P$1") (pintype "bidirectional"))
      (node (ref "P31") (pin "P$2") (pinfunction "2_P$2") (pintype "bidirectional"))
      (node (ref "P31") (pin "P$3") (pinfunction "3_P$3") (pintype "bidirectional"))
    )
    (net (code "59") (name "Net-(P32-1)") (class "Default")
      (node (ref "P32") (pin "P$1") (pinfunction "1_P$1") (pintype "bidirectional"))
      (node (ref "P32") (pin "P$2") (pinfunction "2_P$2") (pintype "bidirectional"))
      (node (ref "P32") (pin "P$3") (pinfunction "3_P$3") (pintype "bidirectional"))
    )
    (net (code "60") (name "Net-(P33-1)") (class "Default")
      (node (ref "P33") (pin "P$1") (pinfunction "1_P$1") (pintype "bidirectional"))
      (node (ref "P33") (pin "P$2") (pinfunction "2_P$2") (pintype "bidirectional"))
      (node (ref "P33") (pin "P$3") (pinfunction "3_P$3") (pintype "bidirectional"))
    )
    (net (code "61") (name "Net-(P34-1)") (class "Default")
      (node (ref "P34") (pin "P$1") (pinfunction "1_P$1") (pintype "bidirectional"))
      (node (ref "P34") (pin "P$2") (pinfunction "2_P$2") (pintype "bidirectional"))
      (node (ref "P34") (pin "P$3") (pinfunction "3_P$3") (pintype "bidirectional"))
    )
    (net (code "62") (name "Net-(P35-1)") (class "Default")
      (node (ref "P35") (pin "P$1") (pinfunction "1_P$1") (pintype "bidirectional"))
      (node (ref "P35") (pin "P$2") (pinfunction "2_P$2") (pintype "bidirectional"))
      (node (ref "P35") (pin "P$3") (pinfunction "3_P$3") (pintype "bidirectional"))
    )
    (net (code "63") (name "Net-(P36-1)") (class "Default")
      (node (ref "P36") (pin "P$1") (pinfunction "1_P$1") (pintype "bidirectional"))
      (node (ref "P36") (pin "P$2") (pinfunction "2_P$2") (pintype "bidirectional"))
      (node (ref "P36") (pin "P$3") (pinfunction "3_P$3") (pintype "bidirectional"))
    )
    (net (code "64") (name "Net-(P37-1)") (class "Default")
      (node (ref "P37") (pin "P$1") (pinfunction "1_P$1") (pintype "bidirectional"))
      (node (ref "P37") (pin "P$2") (pinfunction "2_P$2") (pintype "bidirectional"))
      (node (ref "P37") (pin "P$3") (pinfunction "3_P$3") (pintype "bidirectional"))
    )
    (net (code "65") (name "Net-(P38-1)") (class "Default")
      (node (ref "P38") (pin "P$1") (pinfunction "1_P$1") (pintype "bidirectional"))
      (node (ref "P38") (pin "P$2") (pinfunction "2_P$2") (pintype "bidirectional"))
      (node (ref "P38") (pin "P$3") (pinfunction "3_P$3") (pintype "bidirectional"))
    )
    (net (code "66") (name "Net-(P39-1)") (class "Default")
      (node (ref "P39") (pin "P$1") (pinfunction "1_P$1") (pintype "bidirectional"))
      (node (ref "P39") (pin "P$2") (pinfunction "2_P$2") (pintype "bidirectional"))
      (node (ref "P39") (pin "P$3") (pinfunction "3_P$3") (pintype "bidirectional"))
    )
    (net (code "67") (name "Net-(P40-1)") (class "Default")
      (node (ref "P40") (pin "P$1") (pinfunction "1_P$1") (pintype "bidirectional"))
      (node (ref "P40") (pin "P$2") (pinfunction "2_P$2") (pintype "bidirectional"))
      (node (ref "P40") (pin "P$3") (pinfunction "3_P$3") (pintype "bidirectional"))
    )
    (net (code "68") (name "Net-(P41-1)") (class "Default")
      (node (ref "P41") (pin "P$1") (pinfunction "1_P$1") (pintype "bidirectional"))
      (node (ref "P41") (pin "P$2") (pinfunction "2_P$2") (pintype "bidirectional"))
      (node (ref "P41") (pin "P$3") (pinfunction "3_P$3") (pintype "bidirectional"))
    )
    (net (code "69") (name "Net-(P42-1)") (class "Default")
      (node (ref "P42") (pin "P$1") (pinfunction "1_P$1") (pintype "bidirectional"))
      (node (ref "P42") (pin "P$2") (pinfunction "2_P$2") (pintype "bidirectional"))
      (node (ref "P42") (pin "P$3") (pinfunction "3_P$3") (pintype "bidirectional"))
    )
    (net (code "70") (name "Net-(P43-1)") (class "Default")
      (node (ref "P43") (pin "P$1") (pinfunction "1_P$1") (pintype "bidirectional"))
      (node (ref "P43") (pin "P$2") (pinfunction "2_P$2") (pintype "bidirectional"))
      (node (ref "P43") (pin "P$3") (pinfunction "3_P$3") (pintype "bidirectional"))
    )
    (net (code "71") (name "Net-(P44-1)") (class "Default")
      (node (ref "P44") (pin "P$1") (pinfunction "1_P$1") (pintype "bidirectional"))
      (node (ref "P44") (pin "P$2") (pinfunction "2_P$2") (pintype "bidirectional"))
      (node (ref "P44") (pin "P$3") (pinfunction "3_P$3") (pintype "bidirectional"))
    )
    (net (code "72") (name "Net-(P45-1)") (class "Default")
      (node (ref "P45") (pin "P$1") (pinfunction "1_P$1") (pintype "bidirectional"))
      (node (ref "P45") (pin "P$2") (pinfunction "2_P$2") (pintype "bidirectional"))
      (node (ref "P45") (pin "P$3") (pinfunction "3_P$3") (pintype "bidirectional"))
    )
    (net (code "73") (name "Net-(P46-1)") (class "Default")
      (node (ref "P46") (pin "P$1") (pinfunction "1_P$1") (pintype "bidirectional"))
      (node (ref "P46") (pin "P$2") (pinfunction "2_P$2") (pintype "bidirectional"))
      (node (ref "P46") (pin "P$3") (pinfunction "3_P$3") (pintype "bidirectional"))
    )
    (net (code "74") (name "Net-(P47-1)") (class "Default")
      (node (ref "P47") (pin "P$1") (pinfunction "1_P$1") (pintype "bidirectional"))
      (node (ref "P47") (pin "P$2") (pinfunction "2_P$2") (pintype "bidirectional"))
      (node (ref "P47") (pin "P$3") (pinfunction "3_P$3") (pintype "bidirectional"))
    )
    (net (code "75") (name "Net-(P48-1)") (class "Default")
      (node (ref "P48") (pin "P$1") (pinfunction "1_P$1") (pintype "bidirectional"))
      (node (ref "P48") (pin "P$2") (pinfunction "2_P$2") (pintype "bidirectional"))
      (node (ref "P48") (pin "P$3") (pinfunction "3_P$3") (pintype "bidirectional"))
    )
    (net (code "76") (name "Net-(P49-1)") (class "Default")
      (node (ref "P49") (pin "P$1") (pinfunction "1_P$1") (pintype "bidirectional"))
      (node (ref "P49") (pin "P$2") (pinfunction "2_P$2") (pintype "bidirectional"))
      (node (ref "P49") (pin "P$3") (pinfunction "3_P$3") (pintype "bidirectional"))
    )
    (net (code "77") (name "Net-(P50-1)") (class "Default")
      (node (ref "P50") (pin "P$1") (pinfunction "1_P$1") (pintype "bidirectional"))
      (node (ref "P50") (pin "P$2") (pinfunction "2_P$2") (pintype "bidirectional"))
      (node (ref "P50") (pin "P$3") (pinfunction "3_P$3") (pintype "bidirectional"))
    )
    (net (code "78") (name "Net-(P51-1)") (class "Default")
      (node (ref "P51") (pin "P$1") (pinfunction "1_P$1") (pintype "bidirectional"))
      (node (ref "P51") (pin "P$2") (pinfunction "2_P$2") (pintype "bidirectional"))
      (node (ref "P51") (pin "P$3") (pinfunction "3_P$3") (pintype "bidirectional"))
    )
    (net (code "79") (name "Net-(P52-1)") (class "Default")
      (node (ref "P52") (pin "P$1") (pinfunction "1_P$1") (pintype "bidirectional"))
      (node (ref "P52") (pin "P$2") (pinfunction "2_P$2") (pintype "bidirectional"))
      (node (ref "P52") (pin "P$3") (pinfunction "3_P$3") (pintype "bidirectional"))
    )
    (net (code "80") (name "Net-(P53-1)") (class "Default")
      (node (ref "P53") (pin "P$1") (pinfunction "1_P$1") (pintype "bidirectional"))
      (node (ref "P53") (pin "P$2") (pinfunction "2_P$2") (pintype "bidirectional"))
      (node (ref "P53") (pin "P$3") (pinfunction "3_P$3") (pintype "bidirectional"))
    )
    (net (code "81") (name "Net-(P54-1)") (class "Default")
      (node (ref "P54") (pin "P$1") (pinfunction "1_P$1") (pintype "bidirectional"))
      (node (ref "P54") (pin "P$2") (pinfunction "2_P$2") (pintype "bidirectional"))
      (node (ref "P54") (pin "P$3") (pinfunction "3_P$3") (pintype "bidirectional"))
    )
    (net (code "82") (name "Net-(P55-1)") (class "Default")
      (node (ref "P55") (pin "P$1") (pinfunction "1_P$1") (pintype "bidirectional"))
      (node (ref "P55") (pin "P$2") (pinfunction "2_P$2") (pintype "bidirectional"))
      (node (ref "P55") (pin "P$3") (pinfunction "3_P$3") (pintype "bidirectional"))
    )
    (net (code "83") (name "Net-(P56-1)") (class "Default")
      (node (ref "P56") (pin "P$1") (pinfunction "1_P$1") (pintype "bidirectional"))
      (node (ref "P56") (pin "P$2") (pinfunction "2_P$2") (pintype "bidirectional"))
      (node (ref "P56") (pin "P$3") (pinfunction "3_P$3") (pintype "bidirectional"))
    )
    (net (code "84") (name "Net-(P57-1)") (class "Default")
      (node (ref "P57") (pin "P$1") (pinfunction "1_P$1") (pintype "bidirectional"))
      (node (ref "P57") (pin "P$2") (pinfunction "2_P$2") (pintype "bidirectional"))
      (node (ref "P57") (pin "P$3") (pinfunction "3_P$3") (pintype "bidirectional"))
    )
    (net (code "85") (name "Net-(P58-1)") (class "Default")
      (node (ref "P58") (pin "P$1") (pinfunction "1_P$1") (pintype "bidirectional"))
      (node (ref "P58") (pin "P$2") (pinfunction "2_P$2") (pintype "bidirectional"))
      (node (ref "P58") (pin "P$3") (pinfunction "3_P$3") (pintype "bidirectional"))
    )
    (net (code "86") (name "Net-(P59-1)") (class "Default")
      (node (ref "P59") (pin "P$1") (pinfunction "1_P$1") (pintype "bidirectional"))
      (node (ref "P59") (pin "P$2") (pinfunction "2_P$2") (pintype "bidirectional"))
      (node (ref "P59") (pin "P$3") (pinfunction "3_P$3") (pintype "bidirectional"))
    )
    (net (code "87") (name "Net-(P60-1)") (class "Default")
      (node (ref "P60") (pin "P$1") (pinfunction "1_P$1") (pintype "bidirectional"))
      (node (ref "P60") (pin "P$2") (pinfunction "2_P$2") (pintype "bidirectional"))
      (node (ref "P60") (pin "P$3") (pinfunction "3_P$3") (pintype "bidirectional"))
    )
    (net (code "88") (name "Net-(P61-1)") (class "Default")
      (node (ref "P61") (pin "P$1") (pinfunction "1_P$1") (pintype "bidirectional"))
      (node (ref "P61") (pin "P$2") (pinfunction "2_P$2") (pintype "bidirectional"))
      (node (ref "P61") (pin "P$3") (pinfunction "3_P$3") (pintype "bidirectional"))
    )
    (net (code "89") (name "Net-(P62-1)") (class "Default")
      (node (ref "P62") (pin "P$1") (pinfunction "1_P$1") (pintype "bidirectional"))
      (node (ref "P62") (pin "P$2") (pinfunction "2_P$2") (pintype "bidirectional"))
      (node (ref "P62") (pin "P$3") (pinfunction "3_P$3") (pintype "bidirectional"))
    )
    (net (code "90") (name "Net-(P63-1)") (class "Default")
      (node (ref "P63") (pin "P$1") (pinfunction "1_P$1") (pintype "bidirectional"))
      (node (ref "P63") (pin "P$2") (pinfunction "2_P$2") (pintype "bidirectional"))
      (node (ref "P63") (pin "P$3") (pinfunction "3_P$3") (pintype "bidirectional"))
    )
    (net (code "91") (name "Net-(P64-1)") (class "Default")
      (node (ref "P64") (pin "P$1") (pinfunction "1_P$1") (pintype "bidirectional"))
      (node (ref "P64") (pin "P$2") (pinfunction "2_P$2") (pintype "bidirectional"))
      (node (ref "P64") (pin "P$3") (pinfunction "3_P$3") (pintype "bidirectional"))
    )
    (net (code "92") (name "Net-(P65-1)") (class "Default")
      (node (ref "P65") (pin "P$1") (pinfunction "1_P$1") (pintype "bidirectional"))
      (node (ref "P65") (pin "P$2") (pinfunction "2_P$2") (pintype "bidirectional"))
      (node (ref "P65") (pin "P$3") (pinfunction "3_P$3") (pintype "bidirectional"))
    )
    (net (code "93") (name "Net-(P66-1)") (class "Default")
      (node (ref "P66") (pin "P$1") (pinfunction "1_P$1") (pintype "bidirectional"))
      (node (ref "P66") (pin "P$2") (pinfunction "2_P$2") (pintype "bidirectional"))
      (node (ref "P66") (pin "P$3") (pinfunction "3_P$3") (pintype "bidirectional"))
    )
    (net (code "94") (name "Net-(P67-1)") (class "Default")
      (node (ref "P67") (pin "P$1") (pinfunction "1_P$1") (pintype "bidirectional"))
      (node (ref "P67") (pin "P$2") (pinfunction "2_P$2") (pintype "bidirectional"))
      (node (ref "P67") (pin "P$3") (pinfunction "3_P$3") (pintype "bidirectional"))
    )
    (net (code "95") (name "Net-(P68-1)") (class "Default")
      (node (ref "P68") (pin "P$1") (pinfunction "1_P$1") (pintype "bidirectional"))
      (node (ref "P68") (pin "P$2") (pinfunction "2_P$2") (pintype "bidirectional"))
      (node (ref "P68") (pin "P$3") (pinfunction "3_P$3") (pintype "bidirectional"))
    )
    (net (code "96") (name "Net-(P69-1)") (class "Default")
      (node (ref "P69") (pin "P$1") (pinfunction "1_P$1") (pintype "bidirectional"))
      (node (ref "P69") (pin "P$2") (pinfunction "2_P$2") (pintype "bidirectional"))
      (node (ref "P69") (pin "P$3") (pinfunction "3_P$3") (pintype "bidirectional"))
    )
    (net (code "97") (name "Net-(P70-1)") (class "Default")
      (node (ref "P70") (pin "P$1") (pinfunction "1_P$1") (pintype "bidirectional"))
      (node (ref "P70") (pin "P$2") (pinfunction "2_P$2") (pintype "bidirectional"))
      (node (ref "P70") (pin "P$3") (pinfunction "3_P$3") (pintype "bidirectional"))
    )
    (net (code "98") (name "Net-(P71-1)") (class "Default")
      (node (ref "P71") (pin "P$1") (pinfunction "1_P$1") (pintype "bidirectional"))
      (node (ref "P71") (pin "P$2") (pinfunction "2_P$2") (pintype "bidirectional"))
    )
    (net (code "99") (name "Net-(P72-1)") (class "Default")
      (node (ref "P72") (pin "P$1") (pinfunction "1_P$1") (pintype "bidirectional"))
      (node (ref "P72") (pin "P$2") (pinfunction "2_P$2") (pintype "bidirectional"))
    )
    (net (code "100") (name "Net-(P73-1)") (class "Default")
      (node (ref "P73") (pin "P$1") (pinfunction "1_P$1") (pintype "bidirectional"))
      (node (ref "P73") (pin "P$2") (pinfunction "2_P$2") (pintype "bidirectional"))
    )
    (net (code "101") (name "Net-(P74-1)") (class "Default")
      (node (ref "P74") (pin "P$1") (pinfunction "1_P$1") (pintype "bidirectional"))
      (node (ref "P74") (pin "P$2") (pinfunction "2_P$2") (pintype "bidirectional"))
    )
    (net (code "102") (name "Net-(P75-1)") (class "Default")
      (node (ref "P75") (pin "P$1") (pinfunction "1_P$1") (pintype "bidirectional"))
      (node (ref "P75") (pin "P$2") (pinfunction "2_P$2") (pintype "bidirectional"))
    )
    (net (code "103") (name "Net-(P76-1)") (class "Default")
      (node (ref "P76") (pin "P$1") (pinfunction "1_P$1") (pintype "bidirectional"))
      (node (ref "P76") (pin "P$2") (pinfunction "2_P$2") (pintype "bidirectional"))
    )
    (net (code "104") (name "Net-(P77-1)") (class "Default")
      (node (ref "P77") (pin "P$1") (pinfunction "1_P$1") (pintype "bidirectional"))
      (node (ref "P77") (pin "P$2") (pinfunction "2_P$2") (pintype "bidirectional"))
    )
    (net (code "105") (name "Net-(P78-1)") (class "Default")
      (node (ref "P78") (pin "P$1") (pinfunction "1_P$1") (pintype "bidirectional"))
      (node (ref "P78") (pin "P$2") (pinfunction "2_P$2") (pintype "bidirectional"))
    )
    (net (code "106") (name "Net-(P79-1)") (class "Default")
      (node (ref "P79") (pin "P$1") (pinfunction "1_P$1") (pintype "bidirectional"))
      (node (ref "P79") (pin "P$2") (pinfunction "2_P$2") (pintype "bidirectional"))
    )
    (net (code "107") (name "Net-(P80-1)") (class "Default")
      (node (ref "P80") (pin "P$1") (pinfunction "1_P$1") (pintype "bidirectional"))
      (node (ref "P80") (pin "P$2") (pinfunction "2_P$2") (pintype "bidirectional"))
    )
    (net (code "108") (name "Net-(P81-1)") (class "Default")
      (node (ref "P81") (pin "P$1") (pinfunction "1_P$1") (pintype "bidirectional"))
      (node (ref "P81") (pin "P$2") (pinfunction "2_P$2") (pintype "bidirectional"))
    )
    (net (code "109") (name "Net-(P82-1)") (class "Default")
      (node (ref "P82") (pin "P$1") (pinfunction "1_P$1") (pintype "bidirectional"))
      (node (ref "P82") (pin "P$2") (pinfunction "2_P$2") (pintype "bidirectional"))
    )
    (net (code "110") (name "Net-(P83-1)") (class "Default")
      (node (ref "P83") (pin "P$1") (pinfunction "1_P$1") (pintype "bidirectional"))
      (node (ref "P83") (pin "P$2") (pinfunction "2_P$2") (pintype "bidirectional"))
    )
    (net (code "111") (name "Net-(P84-1)") (class "Default")
      (node (ref "P84") (pin "P$1") (pinfunction "1_P$1") (pintype "bidirectional"))
      (node (ref "P84") (pin "P$2") (pinfunction "2_P$2") (pintype "bidirectional"))
    )
    (net (code "112") (name "Net-(P85-1)") (class "Default")
      (node (ref "P85") (pin "P$1") (pinfunction "1_P$1") (pintype "bidirectional"))
      (node (ref "P85") (pin "P$2") (pinfunction "2_P$2") (pintype "bidirectional"))
    )
    (net (code "113") (name "Net-(P86-1)") (class "Default")
      (node (ref "P86") (pin "P$1") (pinfunction "1_P$1") (pintype "bidirectional"))
      (node (ref "P86") (pin "P$2") (pinfunction "2_P$2") (pintype "bidirectional"))
    )
    (net (code "114") (name "Net-(P87-1)") (class "Default")
      (node (ref "P87") (pin "P$1") (pinfunction "1_P$1") (pintype "bidirectional"))
      (node (ref "P87") (pin "P$2") (pinfunction "2_P$2") (pintype "bidirectional"))
    )
    (net (code "115") (name "Net-(P88-1)") (class "Default")
      (node (ref "P88") (pin "P$1") (pinfunction "1_P$1") (pintype "bidirectional"))
      (node (ref "P88") (pin "P$2") (pinfunction "2_P$2") (pintype "bidirectional"))
    )
    (net (code "116") (name "Net-(P89-1)") (class "Default")
      (node (ref "P89") (pin "P$1") (pinfunction "1_P$1") (pintype "bidirectional"))
      (node (ref "P89") (pin "P$2") (pinfunction "2_P$2") (pintype "bidirectional"))
    )
    (net (code "117") (name "Net-(P90-1)") (class "Default")
      (node (ref "P90") (pin "P$1") (pinfunction "1_P$1") (pintype "bidirectional"))
      (node (ref "P90") (pin "P$2") (pinfunction "2_P$2") (pintype "bidirectional"))
    )
    (net (code "118") (name "Net-(P91-1)") (class "Default")
      (node (ref "P91") (pin "P$1") (pinfunction "1_P$1") (pintype "bidirectional"))
      (node (ref "P91") (pin "P$2") (pinfunction "2_P$2") (pintype "bidirectional"))
    )
    (net (code "119") (name "Net-(P92-1)") (class "Default")
      (node (ref "P92") (pin "P$1") (pinfunction "1_P$1") (pintype "bidirectional"))
      (node (ref "P92") (pin "P$2") (pinfunction "2_P$2") (pintype "bidirectional"))
    )
    (net (code "120") (name "Net-(P93-1)") (class "Default")
      (node (ref "P93") (pin "P$1") (pinfunction "1_P$1") (pintype "bidirectional"))
      (node (ref "P93") (pin "P$2") (pinfunction "2_P$2") (pintype "bidirectional"))
    )
    (net (code "121") (name "Net-(P94-1)") (class "Default")
      (node (ref "P94") (pin "P$1") (pinfunction "1_P$1") (pintype "bidirectional"))
      (node (ref "P94") (pin "P$2") (pinfunction "2_P$2") (pintype "bidirectional"))
    )
    (net (code "122") (name "Net-(P96-1)") (class "Default")
      (node (ref "P96") (pin "P$1") (pinfunction "1_P$1") (pintype "bidirectional"))
      (node (ref "P96") (pin "P$2") (pinfunction "2_P$2") (pintype "bidirectional"))
      (node (ref "P96") (pin "P$3") (pinfunction "3_P$3") (pintype "bidirectional"))
    )
    (net (code "123") (name "Net-(P97-1)") (class "Default")
      (node (ref "P97") (pin "P$1") (pinfunction "1_P$1") (pintype "bidirectional"))
      (node (ref "P97") (pin "P$2") (pinfunction "2_P$2") (pintype "bidirectional"))
      (node (ref "P97") (pin "P$3") (pinfunction "3_P$3") (pintype "bidirectional"))
    )
    (net (code "124") (name "Net-(P98-1)") (class "Default")
      (node (ref "P98") (pin "P$1") (pinfunction "1_P$1") (pintype "bidirectional"))
      (node (ref "P98") (pin "P$2") (pinfunction "2_P$2") (pintype "bidirectional"))
      (node (ref "P98") (pin "P$3") (pinfunction "3_P$3") (pintype "bidirectional"))
    )
    (net (code "125") (name "Net-(P99-1)") (class "Default")
      (node (ref "P99") (pin "P$1") (pinfunction "1_P$1") (pintype "bidirectional"))
      (node (ref "P99") (pin "P$2") (pinfunction "2_P$2") (pintype "bidirectional"))
      (node (ref "P99") (pin "P$3") (pinfunction "3_P$3") (pintype "bidirectional"))
    )
    (net (code "126") (name "Net-(P100-1)") (class "Default")
      (node (ref "P100") (pin "P$1") (pinfunction "1_P$1") (pintype "bidirectional"))
      (node (ref "P100") (pin "P$2") (pinfunction "2_P$2") (pintype "bidirectional"))
      (node (ref "P100") (pin "P$3") (pinfunction "3_P$3") (pintype "bidirectional"))
    )
    (net (code "127") (name "Net-(P101-1)") (class "Default")
      (node (ref "P101") (pin "P$1") (pinfunction "1_P$1") (pintype "bidirectional"))
      (node (ref "P101") (pin "P$2") (pinfunction "2_P$2") (pintype "bidirectional"))
      (node (ref "P101") (pin "P$3") (pinfunction "3_P$3") (pintype "bidirectional"))
    )
    (net (code "128") (name "Net-(P102-1)") (class "Default")
      (node (ref "P102") (pin "P$1") (pinfunction "1_P$1") (pintype "bidirectional"))
      (node (ref "P102") (pin "P$2") (pinfunction "2_P$2") (pintype "bidirectional"))
      (node (ref "P102") (pin "P$3") (pinfunction "3_P$3") (pintype "bidirectional"))
    )
    (net (code "129") (name "Net-(P103-1)") (class "Default")
      (node (ref "P103") (pin "P$1") (pinfunction "1_P$1") (pintype "bidirectional"))
      (node (ref "P103") (pin "P$2") (pinfunction "2_P$2") (pintype "bidirectional"))
      (node (ref "P103") (pin "P$3") (pinfunction "3_P$3") (pintype "bidirectional"))
    )
    (net (code "130") (name "Net-(P104-1)") (class "Default")
      (node (ref "P104") (pin "P$1") (pinfunction "1_P$1") (pintype "bidirectional"))
      (node (ref "P104") (pin "P$2") (pinfunction "2_P$2") (pintype "bidirectional"))
      (node (ref "P104") (pin "P$3") (pinfunction "3_P$3") (pintype "bidirectional"))
    )
    (net (code "131") (name "Net-(P105-1)") (class "Default")
      (node (ref "P105") (pin "P$1") (pinfunction "1_P$1") (pintype "bidirectional"))
      (node (ref "P105") (pin "P$2") (pinfunction "2_P$2") (pintype "bidirectional"))
      (node (ref "P105") (pin "P$3") (pinfunction "3_P$3") (pintype "bidirectional"))
    )
    (net (code "132") (name "Net-(P106-1)") (class "Default")
      (node (ref "P106") (pin "P$1") (pinfunction "1_P$1") (pintype "bidirectional"))
      (node (ref "P106") (pin "P$2") (pinfunction "2_P$2") (pintype "bidirectional"))
      (node (ref "P106") (pin "P$3") (pinfunction "3_P$3") (pintype "bidirectional"))
    )
    (net (code "133") (name "Net-(P107-1)") (class "Default")
      (node (ref "P107") (pin "P$1") (pinfunction "1_P$1") (pintype "bidirectional"))
      (node (ref "P107") (pin "P$2") (pinfunction "2_P$2") (pintype "bidirectional"))
      (node (ref "P107") (pin "P$3") (pinfunction "3_P$3") (pintype "bidirectional"))
    )
    (net (code "134") (name "Net-(P108-1)") (class "Default")
      (node (ref "P108") (pin "P$1") (pinfunction "1_P$1") (pintype "bidirectional"))
      (node (ref "P108") (pin "P$2") (pinfunction "2_P$2") (pintype "bidirectional"))
      (node (ref "P108") (pin "P$3") (pinfunction "3_P$3") (pintype "bidirectional"))
    )
    (net (code "135") (name "Net-(P109-1)") (class "Default")
      (node (ref "P109") (pin "P$1") (pinfunction "1_P$1") (pintype "bidirectional"))
      (node (ref "P109") (pin "P$2") (pinfunction "2_P$2") (pintype "bidirectional"))
      (node (ref "P109") (pin "P$3") (pinfunction "3_P$3") (pintype "bidirectional"))
    )
    (net (code "136") (name "Net-(P110-1)") (class "Default")
      (node (ref "P110") (pin "P$1") (pinfunction "1_P$1") (pintype "bidirectional"))
      (node (ref "P110") (pin "P$2") (pinfunction "2_P$2") (pintype "bidirectional"))
      (node (ref "P110") (pin "P$3") (pinfunction "3_P$3") (pintype "bidirectional"))
    )
    (net (code "137") (name "Net-(P111-1)") (class "Default")
      (node (ref "P111") (pin "P$1") (pinfunction "1_P$1") (pintype "bidirectional"))
      (node (ref "P111") (pin "P$2") (pinfunction "2_P$2") (pintype "bidirectional"))
      (node (ref "P111") (pin "P$3") (pinfunction "3_P$3") (pintype "bidirectional"))
    )
    (net (code "138") (name "Net-(P112-1)") (class "Default")
      (node (ref "P112") (pin "P$1") (pinfunction "1_P$1") (pintype "bidirectional"))
      (node (ref "P112") (pin "P$2") (pinfunction "2_P$2") (pintype "bidirectional"))
      (node (ref "P112") (pin "P$3") (pinfunction "3_P$3") (pintype "bidirectional"))
    )
    (net (code "139") (name "Net-(P113-1)") (class "Default")
      (node (ref "P113") (pin "P$1") (pinfunction "1_P$1") (pintype "bidirectional"))
      (node (ref "P113") (pin "P$2") (pinfunction "2_P$2") (pintype "bidirectional"))
      (node (ref "P113") (pin "P$3") (pinfunction "3_P$3") (pintype "bidirectional"))
    )
    (net (code "140") (name "Net-(P114-1)") (class "Default")
      (node (ref "P114") (pin "P$1") (pinfunction "1_P$1") (pintype "bidirectional"))
      (node (ref "P114") (pin "P$2") (pinfunction "2_P$2") (pintype "bidirectional"))
      (node (ref "P114") (pin "P$3") (pinfunction "3_P$3") (pintype "bidirectional"))
    )
    (net (code "141") (name "Net-(P115-1)") (class "Default")
      (node (ref "P115") (pin "P$1") (pinfunction "1_P$1") (pintype "bidirectional"))
      (node (ref "P115") (pin "P$2") (pinfunction "2_P$2") (pintype "bidirectional"))
      (node (ref "P115") (pin "P$3") (pinfunction "3_P$3") (pintype "bidirectional"))
    )
    (net (code "142") (name "Net-(P116-1)") (class "Default")
      (node (ref "P116") (pin "P$1") (pinfunction "1_P$1") (pintype "bidirectional"))
      (node (ref "P116") (pin "P$2") (pinfunction "2_P$2") (pintype "bidirectional"))
      (node (ref "P116") (pin "P$3") (pinfunction "3_P$3") (pintype "bidirectional"))
    )
    (net (code "143") (name "Net-(P117-1)") (class "Default")
      (node (ref "P117") (pin "P$1") (pinfunction "1_P$1") (pintype "bidirectional"))
      (node (ref "P117") (pin "P$2") (pinfunction "2_P$2") (pintype "bidirectional"))
      (node (ref "P117") (pin "P$3") (pinfunction "3_P$3") (pintype "bidirectional"))
    )
    (net (code "144") (name "Net-(P118-1)") (class "Default")
      (node (ref "P118") (pin "P$1") (pinfunction "1_P$1") (pintype "bidirectional"))
      (node (ref "P118") (pin "P$2") (pinfunction "2_P$2") (pintype "bidirectional"))
      (node (ref "P118") (pin "P$3") (pinfunction "3_P$3") (pintype "bidirectional"))
    )
    (net (code "145") (name "Net-(P120-1)") (class "Default")
      (node (ref "P120") (pin "P$1") (pinfunction "1_P$1") (pintype "bidirectional"))
      (node (ref "P120") (pin "P$2") (pinfunction "2_P$2") (pintype "bidirectional"))
      (node (ref "P120") (pin "P$3") (pinfunction "3_P$3") (pintype "bidirectional"))
    )
    (net (code "146") (name "Net-(P121-1)") (class "Default")
      (node (ref "P121") (pin "P$1") (pinfunction "1_P$1") (pintype "bidirectional"))
      (node (ref "P121") (pin "P$2") (pinfunction "2_P$2") (pintype "bidirectional"))
      (node (ref "P121") (pin "P$3") (pinfunction "3_P$3") (pintype "bidirectional"))
    )
    (net (code "147") (name "Net-(P122-1)") (class "Default")
      (node (ref "P122") (pin "P$1") (pinfunction "1_P$1") (pintype "bidirectional"))
      (node (ref "P122") (pin "P$2") (pinfunction "2_P$2") (pintype "bidirectional"))
      (node (ref "P122") (pin "P$3") (pinfunction "3_P$3") (pintype "bidirectional"))
    )
    (net (code "148") (name "Net-(P123-1)") (class "Default")
      (node (ref "P123") (pin "P$1") (pinfunction "1_P$1") (pintype "bidirectional"))
      (node (ref "P123") (pin "P$2") (pinfunction "2_P$2") (pintype "bidirectional"))
      (node (ref "P123") (pin "P$3") (pinfunction "3_P$3") (pintype "bidirectional"))
    )
    (net (code "149") (name "Net-(P124-1)") (class "Default")
      (node (ref "P124") (pin "P$1") (pinfunction "1_P$1") (pintype "bidirectional"))
      (node (ref "P124") (pin "P$2") (pinfunction "2_P$2") (pintype "bidirectional"))
      (node (ref "P124") (pin "P$3") (pinfunction "3_P$3") (pintype "bidirectional"))
    )
    (net (code "150") (name "Net-(P125-1)") (class "Default")
      (node (ref "P125") (pin "P$1") (pinfunction "1_P$1") (pintype "bidirectional"))
      (node (ref "P125") (pin "P$2") (pinfunction "2_P$2") (pintype "bidirectional"))
      (node (ref "P125") (pin "P$3") (pinfunction "3_P$3") (pintype "bidirectional"))
    )
    (net (code "151") (name "Net-(P126-1)") (class "Default")
      (node (ref "P126") (pin "P$1") (pinfunction "1_P$1") (pintype "bidirectional"))
      (node (ref "P126") (pin "P$2") (pinfunction "2_P$2") (pintype "bidirectional"))
      (node (ref "P126") (pin "P$3") (pinfunction "3_P$3") (pintype "bidirectional"))
    )
  )
)
